# JD1759S-NF-DIS.net
KiCad netlist of a schematic drawn in Altium Designer
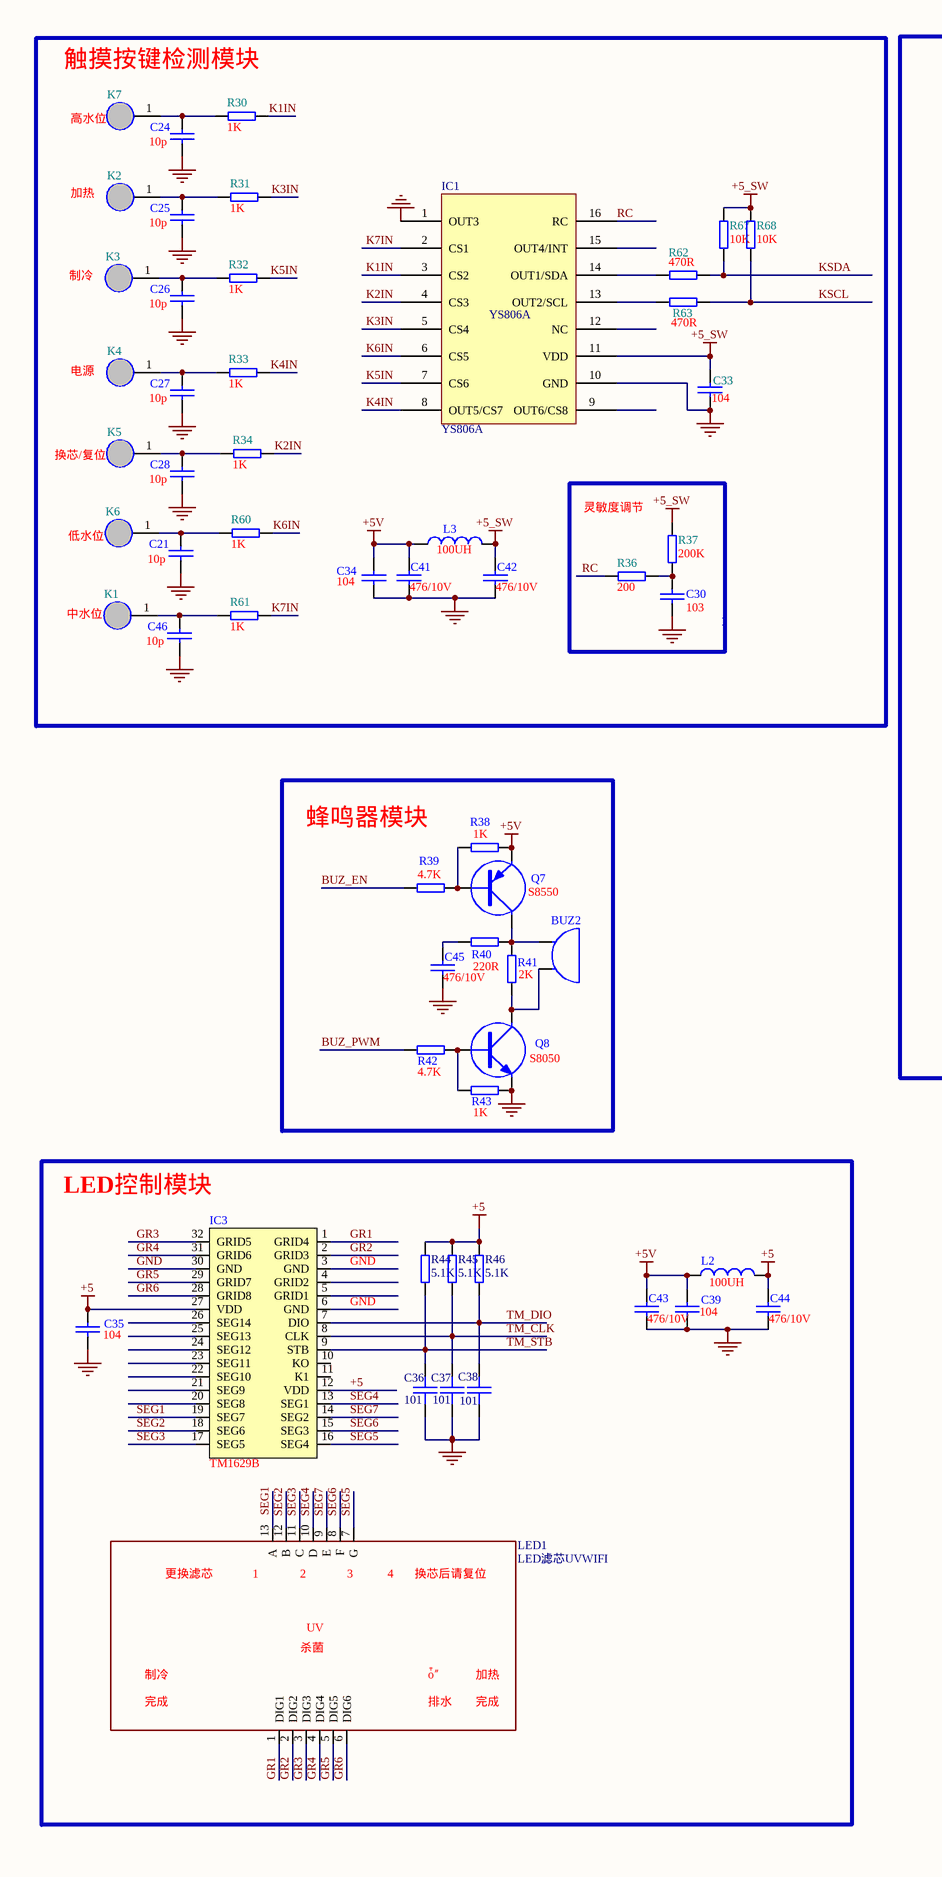
[diagram p0: JD1759S-NF-DIS.SCHDOC, left]
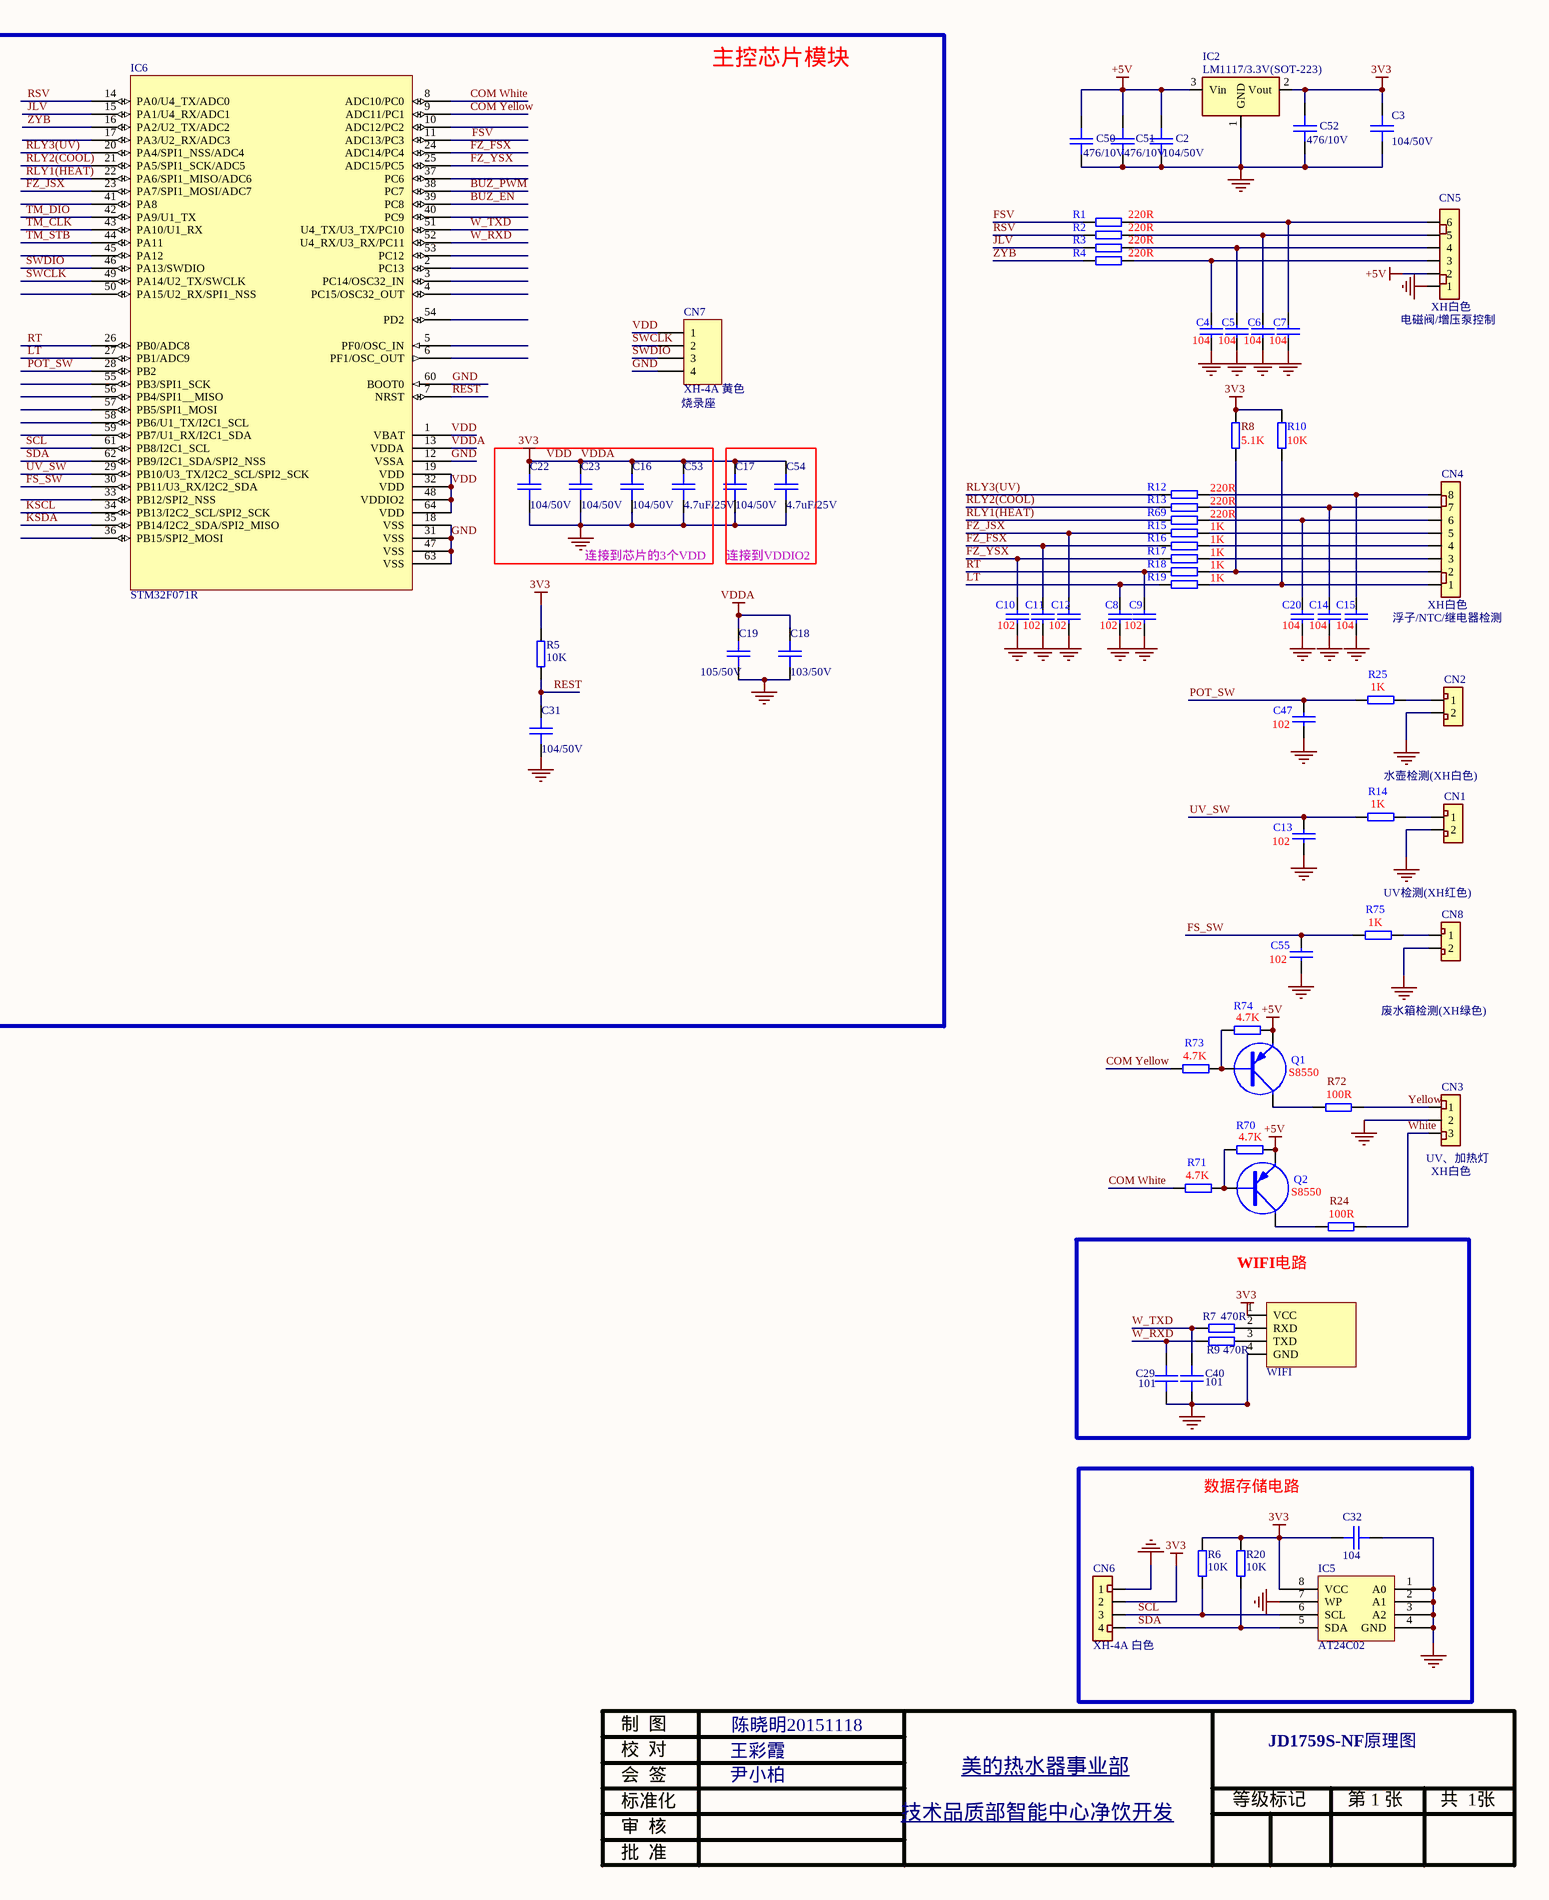
[diagram p1: JD1759S-NF-DIS.SCHDOC, right]

(export (version "E")
  (design (tool "Eeschema 10.0.6"))
  (components
    (comp (ref "BUZ2") (value "~") (footprint "BUZ1") (libsource (lib "*") (part "BUZZER")))
    (comp (ref "C2")
      (value "104/50V")
      (footprint "C0805XG")
      (description "Capacitor")
      (libsource (lib "20131014 MD-SCH") (part "Cap"))
    )
    (comp (ref "C3")
      (value "104/50V")
      (footprint "C0805XG")
      (description "Capacitor (Semiconductor SIM Model)")
      (fields (field (name "PUBLISHER") "*"))
      (libsource (lib "") (part "Cap_1"))
    )
    (comp (ref "C4")
      (value "104")
      (footprint "C0805XG")
      (description "Capacitor")
      (libsource (lib "*") (part "CAP"))
    )
    (comp (ref "C5")
      (value "104")
      (footprint "C0805XG")
      (description "Capacitor")
      (libsource (lib "*") (part "CAP"))
    )
    (comp (ref "C6")
      (value "104")
      (footprint "C0805XG")
      (description "Capacitor")
      (libsource (lib "*") (part "CAP"))
    )
    (comp (ref "C7")
      (value "104")
      (footprint "C0805XG")
      (description "Capacitor")
      (libsource (lib "*") (part "CAP"))
    )
    (comp (ref "C8")
      (value "102")
      (footprint "C0805XG")
      (description "Capacitor")
      (libsource (lib "*") (part "CAP"))
    )
    (comp (ref "C9")
      (value "102")
      (footprint "C0805XG")
      (description "Capacitor")
      (libsource (lib "*") (part "CAP"))
    )
    (comp (ref "C10")
      (value "102")
      (footprint "C0805XG")
      (description "Capacitor")
      (libsource (lib "*") (part "CAP"))
    )
    (comp (ref "C11")
      (value "102")
      (footprint "C0805XG")
      (description "Capacitor")
      (libsource (lib "*") (part "CAP"))
    )
    (comp (ref "C12")
      (value "102")
      (footprint "C0805XG")
      (description "Capacitor")
      (libsource (lib "*") (part "CAP"))
    )
    (comp (ref "C13")
      (value "102")
      (footprint "C0805XG")
      (description "Capacitor")
      (libsource (lib "*") (part "CAP"))
    )
    (comp (ref "C14")
      (value "104")
      (footprint "C0805XG")
      (description "Capacitor")
      (libsource (lib "*") (part "CAP"))
    )
    (comp (ref "C15")
      (value "104")
      (footprint "C0805XG")
      (description "Capacitor")
      (libsource (lib "*") (part "CAP"))
    )
    (comp (ref "C16")
      (value "104/50V")
      (footprint "C0805XG")
      (description "Capacitor")
      (libsource (lib "*") (part "Cap"))
    )
    (comp (ref "C17")
      (value "104/50V")
      (footprint "C0805XG")
      (description "Capacitor")
      (libsource (lib "*") (part "Cap"))
    )
    (comp (ref "C18")
      (value "103/50V")
      (footprint "C0805XG")
      (description "Capacitor")
      (libsource (lib "*") (part "Cap"))
    )
    (comp (ref "C19")
      (value "105/50V")
      (footprint "C0805XG")
      (description "Capacitor")
      (libsource (lib "*") (part "Cap"))
    )
    (comp (ref "C20")
      (value "104")
      (footprint "C0805XG")
      (description "Capacitor")
      (libsource (lib "*") (part "CAP"))
    )
    (comp (ref "C21")
      (value "10p")
      (footprint "C0805XG")
      (description "Capacitor")
      (libsource (lib "*") (part "CAP"))
    )
    (comp (ref "C22")
      (value "104/50V")
      (footprint "C0805XG")
      (description "Capacitor")
      (libsource (lib "*") (part "Cap"))
    )
    (comp (ref "C23")
      (value "104/50V")
      (footprint "C0805XG")
      (description "Capacitor")
      (libsource (lib "*") (part "Cap"))
    )
    (comp (ref "C24")
      (value "10p")
      (footprint "C0805XG")
      (description "Capacitor")
      (libsource (lib "*") (part "CAP"))
    )
    (comp (ref "C25")
      (value "10p")
      (footprint "C0805XG")
      (description "Capacitor")
      (libsource (lib "*") (part "CAP"))
    )
    (comp (ref "C26")
      (value "10p")
      (footprint "C0805XG")
      (description "Capacitor")
      (libsource (lib "*") (part "CAP"))
    )
    (comp (ref "C27")
      (value "10p")
      (footprint "C0805XG")
      (description "Capacitor")
      (libsource (lib "*") (part "CAP"))
    )
    (comp (ref "C28")
      (value "10p")
      (footprint "C0805XG")
      (description "Capacitor")
      (libsource (lib "*") (part "CAP"))
    )
    (comp (ref "C29")
      (value "101")
      (footprint "C0805XG")
      (description "Capacitor")
      (libsource (lib "") (part "Cap_1"))
    )
    (comp (ref "C30") (value "103") (footprint "C0805XG") (libsource (lib "") (part "CAP_3")))
    (comp (ref "C31")
      (value "104/50V")
      (footprint "C0805XG")
      (description "Capacitor")
      (libsource (lib "*") (part "Cap"))
    )
    (comp (ref "C32")
      (value "104")
      (footprint "C0805XG")
      (description "Capacitor")
      (libsource (lib "") (part "Cap_1"))
    )
    (comp (ref "C33") (value "104") (footprint "C0805XG") (libsource (lib "*") (part "C")))
    (comp (ref "C34") (value "104") (footprint "C0805XG") (libsource (lib "") (part "CAP_1")))
    (comp (ref "C35") (value "104") (footprint "C0805XG") (libsource (lib "") (part "CAP_1")))
    (comp (ref "C36")
      (value "101")
      (footprint "C0805XG")
      (description "CAP")
      (libsource (lib "") (part "CAP_2"))
    )
    (comp (ref "C37")
      (value "101")
      (footprint "C0805XG")
      (description "CAP")
      (libsource (lib "") (part "CAP_2"))
    )
    (comp (ref "C38")
      (value "101")
      (footprint "C0805XG")
      (description "CAP")
      (libsource (lib "") (part "CAP_2"))
    )
    (comp (ref "C39") (value "104") (footprint "C0805XG") (libsource (lib "") (part "CAP_1")))
    (comp (ref "C40")
      (value "101")
      (footprint "C0805XG")
      (description "Capacitor")
      (libsource (lib "") (part "Cap_1"))
    )
    (comp (ref "C41") (value "476/10V") (footprint "C1206") (libsource (lib "") (part "CAP_1")))
    (comp (ref "C42") (value "476/10V") (footprint "C1206") (libsource (lib "") (part "CAP_1")))
    (comp (ref "C43") (value "476/10V") (footprint "C1206") (libsource (lib "") (part "CAP_1")))
    (comp (ref "C44") (value "476/10V") (footprint "C1206") (libsource (lib "") (part "CAP_1")))
    (comp (ref "C45") (value "476/10V") (footprint "C1206") (libsource (lib "") (part "CAP_1")))
    (comp (ref "C46")
      (value "10p")
      (footprint "C0805XG")
      (description "Capacitor")
      (libsource (lib "*") (part "CAP"))
    )
    (comp (ref "C47")
      (value "102")
      (footprint "C0805XG")
      (description "Capacitor")
      (libsource (lib "*") (part "CAP"))
    )
    (comp (ref "C50")
      (value "476/10V")
      (footprint "C1206")
      (description "Capacitor")
      (libsource (lib "20131014 MD-SCH") (part "Cap"))
    )
    (comp (ref "C51")
      (value "476/10V")
      (footprint "C1206")
      (description "Capacitor")
      (libsource (lib "20131014 MD-SCH") (part "Cap"))
    )
    (comp (ref "C52")
      (value "476/10V")
      (footprint "C1206")
      (description "Capacitor")
      (libsource (lib "20131014 MD-SCH") (part "Cap"))
    )
    (comp (ref "C53")
      (value "4.7uF/25V")
      (footprint "C0805XG")
      (description "Capacitor")
      (libsource (lib "*") (part "Cap"))
    )
    (comp (ref "C54")
      (value "4.7uF/25V")
      (footprint "C0805XG")
      (description "Capacitor")
      (libsource (lib "*") (part "Cap"))
    )
    (comp (ref "C55")
      (value "102")
      (footprint "C0805XG")
      (description "Capacitor")
      (libsource (lib "*") (part "CAP"))
    )
    (comp (ref "CN1") (value "CN2") (footprint "CN2") (libsource (lib "20131014 MD-SCH") (part "CN2")))
    (comp (ref "CN2") (value "CN2") (footprint "CN2") (libsource (lib "20131014 MD-SCH") (part "CN2")))
    (comp (ref "CN3") (value "CN3") (footprint "CN3") (libsource (lib "20131014 MD-SCH") (part "CN3")))
    (comp (ref "CN4")
      (value "XH白色")
      (footprint "CN8")
      (description "CN8")
      (libsource (lib "20131014 MD-SCH") (part "CN8"))
    )
    (comp (ref "CN5")
      (value "XH白色")
      (footprint "CN6")
      (description "CN6")
      (libsource (lib "20131014 MD-SCH") (part "CN6"))
    )
    (comp (ref "CN6")
      (value "XH-4A 白色")
      (footprint "CN4")
      (description "CN4")
      (libsource (lib "20131014 MD-SCH") (part "CN4"))
    )
    (comp (ref "CN7")
      (value "XH-4A 黄色")
      (footprint "CN4")
      (description "Header, 4-Pin")
      (fields (field (name "PUBLISHER") "Altium Limited"))
      (libsource (lib "*") (part "Header 4"))
    )
    (comp (ref "CN8") (value "CN2") (footprint "CN2") (libsource (lib "20131014 MD-SCH") (part "CN2")))
    (comp (ref "IC1")
      (value "YS806A")
      (footprint "SOP16")
      (libsource (lib "20131014 MD-SCH") (part "YS806A"))
    )
    (comp (ref "IC2")
      (value "LM1117/3.3V(SOT-223)")
      (footprint "SOT-223")
      (libsource (lib "*") (part "SOT-223"))
    )
    (comp (ref "IC3") (value "TM1629B") (footprint "SOP32") (libsource (lib "*") (part "TM1629B")))
    (comp (ref "IC4") (value "WIFI") (footprint "WIFI") (libsource (lib "xxyj_schlib") (part "WIFI")))
    (comp (ref "IC5") (value "AT24C02") (footprint "SOP8") (libsource (lib "*") (part "Component_1")))
    (comp (ref "IC6")
      (value "STM32F071R")
      (footprint "QFP64(0.5MM)")
      (libsource (lib "*") (part "STM32F071R"))
    )
    (comp (ref "K1") (value "中水位") (footprint "KEY-T1 - 12") (libsource (lib "*") (part "1P-TOUCH")))
    (comp (ref "K2") (value "加热") (footprint "KEY-T1 - 12") (libsource (lib "*") (part "1P-TOUCH")))
    (comp (ref "K3") (value "制冷") (footprint "KEY-T1 - 12") (libsource (lib "*") (part "1P-TOUCH")))
    (comp (ref "K4") (value "电源") (footprint "KEY-T1 - 12") (libsource (lib "*") (part "1P-TOUCH")))
    (comp (ref "K5") (value "换芯/复位") (footprint "KEY-T1 - 12") (libsource (lib "*") (part "1P-TOUCH")))
    (comp (ref "K6") (value "低水位") (footprint "KEY-T1 - 12") (libsource (lib "*") (part "1P-TOUCH")))
    (comp (ref "K7") (value "高水位") (footprint "KEY-T1 - 12") (libsource (lib "*") (part "1P-TOUCH")))
    (comp (ref "L2")
      (value "100UH")
      (footprint "L100-5.7")
      (description "LOOP")
      (libsource (lib "*") (part "L-B"))
    )
    (comp (ref "L3")
      (value "100UH")
      (footprint "R1210")
      (description "LOOP")
      (libsource (lib "*") (part "L-B"))
    )
    (comp (ref "LED1")
      (value "LED滤芯UVWIFI")
      (footprint "LED滤芯UVWIFI")
      (description "LED888")
      (libsource (lib "20131014 MD-SCH") (part "LED滤芯UVWIFI"))
    )
    (comp (ref "Q1") (value "S8550") (footprint "SOT23-BCE") (libsource (lib "*") (part "PNP")))
    (comp (ref "Q2") (value "S8550") (footprint "SOT23-BCE") (libsource (lib "*") (part "PNP")))
    (comp (ref "Q7") (value "S8550") (footprint "SOT23-BCE") (libsource (lib "*") (part "PNP")))
    (comp (ref "Q8") (value "S8050") (footprint "SOT23-BCE") (libsource (lib "*") (part "NPN")))
    (comp (ref "R1")
      (value "220R")
      (footprint "R0805XG")
      (description "RES")
      (libsource (lib "*") (part "RES1"))
    )
    (comp (ref "R2")
      (value "220R")
      (footprint "R0805XG")
      (description "RES")
      (libsource (lib "*") (part "RES1"))
    )
    (comp (ref "R3")
      (value "220R")
      (footprint "R0805XG")
      (description "RES")
      (libsource (lib "*") (part "RES1"))
    )
    (comp (ref "R4")
      (value "220R")
      (footprint "R0805XG")
      (description "RES")
      (libsource (lib "*") (part "RES1"))
    )
    (comp (ref "R5")
      (value "10K")
      (footprint "R0805XG")
      (description "RES")
      (libsource (lib "*") (part "RES1"))
    )
    (comp (ref "R6")
      (value "10K")
      (footprint "R0805XG")
      (description "RES")
      (libsource (lib "*") (part "RES1"))
    )
    (comp (ref "R7")
      (value "470R")
      (footprint "R0805XG")
      (description "RES")
      (libsource (lib "*") (part "RES1"))
    )
    (comp (ref "R8")
      (value "5.1K")
      (footprint "R0805XG")
      (description "RES")
      (libsource (lib "*") (part "RES1"))
    )
    (comp (ref "R9")
      (value "470R")
      (footprint "R0805XG")
      (description "RES")
      (libsource (lib "*") (part "RES1"))
    )
    (comp (ref "R10")
      (value "10K")
      (footprint "R0805XG")
      (description "RES")
      (libsource (lib "*") (part "RES1"))
    )
    (comp (ref "R12")
      (value "220R")
      (footprint "R0805XG")
      (description "RES")
      (libsource (lib "*") (part "RES1"))
    )
    (comp (ref "R13")
      (value "220R")
      (footprint "R0805XG")
      (description "RES")
      (libsource (lib "*") (part "RES1"))
    )
    (comp (ref "R14")
      (value "1K")
      (footprint "R0805XG")
      (description "RES")
      (libsource (lib "*") (part "RES1"))
    )
    (comp (ref "R15")
      (value "1K")
      (footprint "R0805XG")
      (description "RES")
      (libsource (lib "*") (part "RES1"))
    )
    (comp (ref "R16")
      (value "1K")
      (footprint "R0805XG")
      (description "RES")
      (libsource (lib "*") (part "RES1"))
    )
    (comp (ref "R17")
      (value "1K")
      (footprint "R0805XG")
      (description "RES")
      (libsource (lib "*") (part "RES1"))
    )
    (comp (ref "R18")
      (value "1K")
      (footprint "R0805XG")
      (description "RES")
      (libsource (lib "*") (part "RES1"))
    )
    (comp (ref "R19")
      (value "1K")
      (footprint "R0805XG")
      (description "RES")
      (libsource (lib "*") (part "RES1"))
    )
    (comp (ref "R20")
      (value "10K")
      (footprint "R0805XG")
      (description "RES")
      (libsource (lib "*") (part "RES1"))
    )
    (comp (ref "R24")
      (value "100R")
      (footprint "R1206")
      (description "RES")
      (libsource (lib "*") (part "RES1"))
    )
    (comp (ref "R25")
      (value "1K")
      (footprint "R0805XG")
      (description "RES")
      (libsource (lib "*") (part "RES1"))
    )
    (comp (ref "R30")
      (value "1K")
      (footprint "R0805XG")
      (description "RES")
      (libsource (lib "*") (part "RES1"))
    )
    (comp (ref "R31")
      (value "1K")
      (footprint "R0805XG")
      (description "RES")
      (libsource (lib "*") (part "RES1"))
    )
    (comp (ref "R32")
      (value "1K")
      (footprint "R0805XG")
      (description "RES")
      (libsource (lib "*") (part "RES1"))
    )
    (comp (ref "R33")
      (value "1K")
      (footprint "R0805XG")
      (description "RES")
      (libsource (lib "*") (part "RES1"))
    )
    (comp (ref "R34")
      (value "1K")
      (footprint "R0805XG")
      (description "RES")
      (libsource (lib "*") (part "RES1"))
    )
    (comp (ref "R36")
      (value "200")
      (footprint "R0805XG")
      (description "RES")
      (libsource (lib "*") (part "RES1"))
    )
    (comp (ref "R37")
      (value "200K")
      (footprint "R0805XG")
      (description "RES")
      (libsource (lib "*") (part "RES1"))
    )
    (comp (ref "R38")
      (value "1K")
      (footprint "R0805XG")
      (description "RES")
      (libsource (lib "*") (part "RES1"))
    )
    (comp (ref "R39")
      (value "4.7K")
      (footprint "R0805XG")
      (description "RES")
      (libsource (lib "*") (part "RES1"))
    )
    (comp (ref "R40")
      (value "220R")
      (footprint "R0805XG")
      (description "RES")
      (libsource (lib "*") (part "RES1"))
    )
    (comp (ref "R41")
      (value "2K")
      (footprint "R0805XG")
      (description "RES")
      (libsource (lib "*") (part "RES1"))
    )
    (comp (ref "R42")
      (value "4.7K")
      (footprint "R0805XG")
      (description "RES")
      (libsource (lib "*") (part "RES1"))
    )
    (comp (ref "R43")
      (value "1K")
      (footprint "R0805XG")
      (description "RES")
      (libsource (lib "*") (part "RES1"))
    )
    (comp (ref "R44")
      (value "5.1K")
      (footprint "R0805XG")
      (description "RES")
      (libsource (lib "*") (part "RES1"))
    )
    (comp (ref "R45")
      (value "5.1K")
      (footprint "R0805XG")
      (description "RES")
      (libsource (lib "*") (part "RES1"))
    )
    (comp (ref "R46")
      (value "5.1K")
      (footprint "R0805XG")
      (description "RES")
      (libsource (lib "*") (part "RES1"))
    )
    (comp (ref "R60")
      (value "1K")
      (footprint "R0805XG")
      (description "RES")
      (libsource (lib "*") (part "RES1"))
    )
    (comp (ref "R61")
      (value "1K")
      (footprint "R0805XG")
      (description "RES")
      (libsource (lib "*") (part "RES1"))
    )
    (comp (ref "R62")
      (value "470R")
      (footprint "R0805XG")
      (description "RES")
      (libsource (lib "*") (part "RES1"))
    )
    (comp (ref "R63")
      (value "470R")
      (footprint "R0805XG")
      (description "RES")
      (libsource (lib "*") (part "RES1"))
    )
    (comp (ref "R67")
      (value "10K")
      (footprint "R0805XG")
      (description "RES")
      (libsource (lib "*") (part "RES1"))
    )
    (comp (ref "R68")
      (value "10K")
      (footprint "R0805XG")
      (description "RES")
      (libsource (lib "*") (part "RES1"))
    )
    (comp (ref "R69")
      (value "220R")
      (footprint "R0805XG")
      (description "RES")
      (libsource (lib "*") (part "RES1"))
    )
    (comp (ref "R70")
      (value "4.7K")
      (footprint "R0805XG")
      (description "RES")
      (libsource (lib "*") (part "RES1"))
    )
    (comp (ref "R71")
      (value "4.7K")
      (footprint "R0805XG")
      (description "RES")
      (libsource (lib "*") (part "RES1"))
    )
    (comp (ref "R72")
      (value "100R")
      (footprint "R1206")
      (description "RES")
      (libsource (lib "*") (part "RES1"))
    )
    (comp (ref "R73")
      (value "4.7K")
      (footprint "R0805XG")
      (description "RES")
      (libsource (lib "*") (part "RES1"))
    )
    (comp (ref "R74")
      (value "4.7K")
      (footprint "R0805XG")
      (description "RES")
      (libsource (lib "*") (part "RES1"))
    )
    (comp (ref "R75")
      (value "1K")
      (footprint "R0805XG")
      (description "RES")
      (libsource (lib "*") (part "RES1"))
    )
  )
  (nets
    (net (code "1") (name "+5") (class "Default")
      (node (ref "C35") (pin "2") (pintype "passive"))
      (node (ref "C44") (pin "2") (pintype "passive"))
      (node (ref "IC3") (pin "12") (pinfunction "VDD_12") (pintype "passive"))
      (node (ref "IC3") (pin "27") (pinfunction "VDD_27") (pintype "passive"))
      (node (ref "L2") (pin "1") (pinfunction "1_1") (pintype "passive"))
      (node (ref "R44") (pin "2") (pinfunction "2_2") (pintype "passive"))
      (node (ref "R45") (pin "2") (pinfunction "2_2") (pintype "passive"))
      (node (ref "R46") (pin "2") (pinfunction "2_2") (pintype "passive"))
    )
    (net (code "2") (name "+5V") (class "Default")
      (node (ref "C2") (pin "2") (pinfunction "2_2") (pintype "passive"))
      (node (ref "C34") (pin "2") (pintype "passive"))
      (node (ref "C39") (pin "2") (pintype "passive"))
      (node (ref "C41") (pin "2") (pintype "passive"))
      (node (ref "C43") (pin "2") (pintype "passive"))
      (node (ref "C50") (pin "2") (pinfunction "2_2") (pintype "passive"))
      (node (ref "C51") (pin "2") (pinfunction "2_2") (pintype "passive"))
      (node (ref "CN5") (pin "2") (pinfunction "2_2") (pintype "passive"))
      (node (ref "IC2") (pin "3") (pinfunction "Vin_3") (pintype "passive"))
      (node (ref "L2") (pin "2") (pinfunction "2_2") (pintype "passive"))
      (node (ref "L3") (pin "2") (pinfunction "2_2") (pintype "passive"))
      (node (ref "Q1") (pin "E") (pintype "passive"))
      (node (ref "Q2") (pin "E") (pintype "passive"))
      (node (ref "Q7") (pin "E") (pintype "passive"))
      (node (ref "R38") (pin "2") (pinfunction "2_2") (pintype "passive"))
      (node (ref "R70") (pin "2") (pinfunction "2_2") (pintype "passive"))
      (node (ref "R74") (pin "2") (pinfunction "2_2") (pintype "passive"))
    )
    (net (code "3") (name "+5_SW") (class "Default")
      (node (ref "C33") (pin "2") (pintype "passive"))
      (node (ref "C42") (pin "2") (pintype "passive"))
      (node (ref "IC1") (pin "11") (pinfunction "VDD_11") (pintype "passive"))
      (node (ref "L3") (pin "1") (pinfunction "1_1") (pintype "passive"))
      (node (ref "R37") (pin "1") (pinfunction "1_1") (pintype "passive"))
      (node (ref "R67") (pin "1") (pinfunction "1_1") (pintype "passive"))
      (node (ref "R68") (pin "1") (pinfunction "1_1") (pintype "passive"))
    )
    (net (code "5") (name "/BUZ_EN") (class "Default")
      (node (ref "IC6") (pin "39") (pinfunction "PC8_39") (pintype "bidirectional"))
      (node (ref "R39") (pin "1") (pinfunction "1_1") (pintype "passive"))
    )
    (net (code "6") (name "/BUZ_PWM") (class "Default")
      (node (ref "IC6") (pin "38") (pinfunction "PC7_38") (pintype "bidirectional"))
      (node (ref "R42") (pin "1") (pinfunction "1_1") (pintype "passive"))
    )
    (net (code "7") (name "/COM White") (class "Default")
      (node (ref "IC6") (pin "8") (pinfunction "ADC10/PC0_8") (pintype "bidirectional"))
      (node (ref "R71") (pin "1") (pinfunction "1_1") (pintype "passive"))
    )
    (net (code "8") (name "/COM Yellow") (class "Default")
      (node (ref "IC6") (pin "9") (pinfunction "ADC11/PC1_9") (pintype "bidirectional"))
      (node (ref "R73") (pin "1") (pinfunction "1_1") (pintype "passive"))
    )
    (net (code "9") (name "/FSV") (class "Default")
      (node (ref "IC6") (pin "11") (pinfunction "ADC13/PC3_11") (pintype "bidirectional"))
      (node (ref "R1") (pin "2") (pinfunction "2_2") (pintype "passive"))
    )
    (net (code "10") (name "/FS_SW") (class "Default")
      (node (ref "C55") (pin "1") (pinfunction "1_1") (pintype "passive"))
      (node (ref "IC6") (pin "30") (pinfunction "PB11/U3_RX/I2C2_SDA_30") (pintype "bidirectional"))
      (node (ref "R75") (pin "2") (pinfunction "2_2") (pintype "passive"))
    )
    (net (code "11") (name "/FZ_FSX") (class "Default")
      (node (ref "C11") (pin "1") (pinfunction "1_1") (pintype "passive"))
      (node (ref "IC6") (pin "24") (pinfunction "ADC14/PC4_24") (pintype "bidirectional"))
      (node (ref "R16") (pin "2") (pinfunction "2_2") (pintype "passive"))
    )
    (net (code "12") (name "/FZ_JSX") (class "Default")
      (node (ref "C12") (pin "1") (pinfunction "1_1") (pintype "passive"))
      (node (ref "IC6") (pin "23") (pinfunction "PA7/SPI1_MOSI/ADC7_23") (pintype "bidirectional"))
      (node (ref "R15") (pin "2") (pinfunction "2_2") (pintype "passive"))
    )
    (net (code "13") (name "/FZ_YSX") (class "Default")
      (node (ref "C10") (pin "1") (pinfunction "1_1") (pintype "passive"))
      (node (ref "IC6") (pin "25") (pinfunction "ADC15/PC5_25") (pintype "bidirectional"))
      (node (ref "R17") (pin "2") (pinfunction "2_2") (pintype "passive"))
    )
    (net (code "14") (name "/GR1") (class "Default")
      (node (ref "IC3") (pin "1") (pinfunction "GRID4_1") (pintype "passive"))
      (node (ref "LED1") (pin "1") (pinfunction "DIG1_1") (pintype "passive"))
    )
    (net (code "15") (name "/GR2") (class "Default")
      (node (ref "IC3") (pin "2") (pinfunction "GRID3_2") (pintype "passive"))
      (node (ref "LED1") (pin "2") (pinfunction "DIG2_2") (pintype "passive"))
    )
    (net (code "16") (name "/GR3") (class "Default")
      (node (ref "IC3") (pin "32") (pinfunction "GRID5_32") (pintype "passive"))
      (node (ref "LED1") (pin "3") (pinfunction "DIG3_3") (pintype "passive"))
    )
    (net (code "17") (name "/GR4") (class "Default")
      (node (ref "IC3") (pin "31") (pinfunction "GRID6_31") (pintype "passive"))
      (node (ref "LED1") (pin "4") (pinfunction "DIG4_4") (pintype "passive"))
    )
    (net (code "18") (name "/GR5") (class "Default")
      (node (ref "IC3") (pin "29") (pinfunction "GRID7_29") (pintype "passive"))
      (node (ref "LED1") (pin "5") (pinfunction "DIG5_5") (pintype "passive"))
    )
    (net (code "19") (name "/GR6") (class "Default")
      (node (ref "IC3") (pin "28") (pinfunction "GRID8_28") (pintype "passive"))
      (node (ref "LED1") (pin "6") (pinfunction "DIG6_6") (pintype "passive"))
    )
    (net (code "20") (name "/JLV") (class "Default")
      (node (ref "IC6") (pin "15") (pinfunction "PA1/U4_RX/ADC1_15") (pintype "bidirectional"))
      (node (ref "R3") (pin "2") (pinfunction "2_2") (pintype "passive"))
    )
    (net (code "21") (name "/K1IN") (class "Default")
      (node (ref "IC1") (pin "3") (pinfunction "CS2_3") (pintype "passive"))
      (node (ref "R30") (pin "2") (pinfunction "2_2") (pintype "passive"))
    )
    (net (code "22") (name "/K2IN") (class "Default")
      (node (ref "IC1") (pin "4") (pinfunction "CS3_4") (pintype "passive"))
      (node (ref "R34") (pin "1") (pinfunction "1_1") (pintype "passive"))
    )
    (net (code "23") (name "/K3IN") (class "Default")
      (node (ref "IC1") (pin "5") (pinfunction "CS4_5") (pintype "passive"))
      (node (ref "R31") (pin "1") (pinfunction "1_1") (pintype "passive"))
    )
    (net (code "24") (name "/K4IN") (class "Default")
      (node (ref "IC1") (pin "8") (pinfunction "OUT5/CS7_8") (pintype "passive"))
      (node (ref "R33") (pin "1") (pinfunction "1_1") (pintype "passive"))
    )
    (net (code "25") (name "/K5IN") (class "Default")
      (node (ref "IC1") (pin "7") (pinfunction "CS6_7") (pintype "passive"))
      (node (ref "R32") (pin "1") (pinfunction "1_1") (pintype "passive"))
    )
    (net (code "26") (name "/K6IN") (class "Default")
      (node (ref "IC1") (pin "6") (pinfunction "CS5_6") (pintype "passive"))
      (node (ref "R60") (pin "1") (pinfunction "1_1") (pintype "passive"))
    )
    (net (code "27") (name "/K7IN") (class "Default")
      (node (ref "IC1") (pin "2") (pinfunction "CS1_2") (pintype "passive"))
      (node (ref "R61") (pin "1") (pinfunction "1_1") (pintype "passive"))
    )
    (net (code "28") (name "/KSCL") (class "Default")
      (node (ref "IC6") (pin "34") (pinfunction "PB13/I2C2_SCL/SPI2_SCK_34") (pintype "bidirectional"))
      (node (ref "R63") (pin "1") (pinfunction "1_1") (pintype "passive"))
      (node (ref "R68") (pin "2") (pinfunction "2_2") (pintype "passive"))
    )
    (net (code "29") (name "/KSDA") (class "Default")
      (node (ref "IC6") (pin "35") (pinfunction "PB14/I2C2_SDA/SPI2_MISO_35") (pintype "bidirectional"))
      (node (ref "R62") (pin "1") (pinfunction "1_1") (pintype "passive"))
      (node (ref "R67") (pin "2") (pinfunction "2_2") (pintype "passive"))
    )
    (net (code "30") (name "/LT") (class "Default")
      (node (ref "C8") (pin "1") (pinfunction "1_1") (pintype "passive"))
      (node (ref "IC6") (pin "27") (pinfunction "PB1/ADC9_27") (pintype "bidirectional"))
      (node (ref "R19") (pin "2") (pinfunction "2_2") (pintype "passive"))
    )
    (net (code "31") (name "/POT_SW") (class "Default")
      (node (ref "C47") (pin "1") (pinfunction "1_1") (pintype "passive"))
      (node (ref "IC6") (pin "28") (pinfunction "PB2_28") (pintype "bidirectional"))
      (node (ref "R25") (pin "2") (pinfunction "2_2") (pintype "passive"))
    )
    (net (code "32") (name "/RC") (class "Default")
      (node (ref "IC1") (pin "16") (pinfunction "RC_16") (pintype "passive"))
      (node (ref "R36") (pin "1") (pinfunction "1_1") (pintype "passive"))
    )
    (net (code "33") (name "/REST") (class "Default")
      (node (ref "C31") (pin "2") (pinfunction "2_2") (pintype "passive"))
      (node (ref "IC6") (pin "7") (pinfunction "NRST_7") (pintype "bidirectional"))
      (node (ref "R5") (pin "2") (pinfunction "2_2") (pintype "passive"))
    )
    (net (code "34") (name "/RLY1(HEAT)") (class "Default")
      (node (ref "IC6") (pin "22") (pinfunction "PA6/SPI1_MISO/ADC6_22") (pintype "bidirectional"))
      (node (ref "R69") (pin "2") (pinfunction "2_2") (pintype "passive"))
    )
    (net (code "35") (name "/RLY2(COOL)") (class "Default")
      (node (ref "IC6") (pin "21") (pinfunction "PA5/SPI1_SCK/ADC5_21") (pintype "bidirectional"))
      (node (ref "R13") (pin "2") (pinfunction "2_2") (pintype "passive"))
    )
    (net (code "36") (name "/RLY3(UV)") (class "Default")
      (node (ref "IC6") (pin "20") (pinfunction "PA4/SPI1_NSS/ADC4_20") (pintype "bidirectional"))
      (node (ref "R12") (pin "2") (pinfunction "2_2") (pintype "passive"))
    )
    (net (code "37") (name "/RSV") (class "Default")
      (node (ref "IC6") (pin "14") (pinfunction "PA0/U4_TX/ADC0_14") (pintype "bidirectional"))
      (node (ref "R2") (pin "2") (pinfunction "2_2") (pintype "passive"))
    )
    (net (code "38") (name "/RT") (class "Default")
      (node (ref "C9") (pin "1") (pinfunction "1_1") (pintype "passive"))
      (node (ref "IC6") (pin "26") (pinfunction "PB0/ADC8_26") (pintype "bidirectional"))
      (node (ref "R18") (pin "2") (pinfunction "2_2") (pintype "passive"))
    )
    (net (code "39") (name "/SCL") (class "Default")
      (node (ref "CN6") (pin "3") (pinfunction "3_3") (pintype "passive"))
      (node (ref "IC5") (pin "6") (pinfunction "SCL_6") (pintype "passive"))
      (node (ref "IC6") (pin "61") (pinfunction "PB8/I2C1_SCL_61") (pintype "bidirectional"))
      (node (ref "R6") (pin "1") (pinfunction "1_1") (pintype "passive"))
    )
    (net (code "40") (name "/SDA") (class "Default")
      (node (ref "CN6") (pin "4") (pinfunction "4_4") (pintype "passive"))
      (node (ref "IC5") (pin "5") (pinfunction "SDA_5") (pintype "passive"))
      (node (ref "IC6") (pin "62") (pinfunction "PB9/I2C1_SDA/SPI2_NSS_62") (pintype "bidirectional"))
      (node (ref "R20") (pin "1") (pinfunction "1_1") (pintype "passive"))
    )
    (net (code "41") (name "/SEG1") (class "Default")
      (node (ref "IC3") (pin "19") (pinfunction "SEG7_19") (pintype "passive"))
      (node (ref "LED1") (pin "13") (pinfunction "A_13") (pintype "passive"))
    )
    (net (code "42") (name "/SEG2") (class "Default")
      (node (ref "IC3") (pin "18") (pinfunction "SEG6_18") (pintype "passive"))
      (node (ref "LED1") (pin "12") (pinfunction "B_12") (pintype "passive"))
    )
    (net (code "43") (name "/SEG3") (class "Default")
      (node (ref "IC3") (pin "17") (pinfunction "SEG5_17") (pintype "passive"))
      (node (ref "LED1") (pin "11") (pinfunction "C_11") (pintype "passive"))
    )
    (net (code "44") (name "/SEG4") (class "Default")
      (node (ref "IC3") (pin "13") (pinfunction "SEG1_13") (pintype "passive"))
      (node (ref "LED1") (pin "10") (pinfunction "D_10") (pintype "passive"))
    )
    (net (code "45") (name "/SEG5") (class "Default")
      (node (ref "IC3") (pin "16") (pinfunction "SEG4_16") (pintype "passive"))
      (node (ref "LED1") (pin "7") (pinfunction "G_7") (pintype "passive"))
    )
    (net (code "46") (name "/SEG6") (class "Default")
      (node (ref "IC3") (pin "15") (pinfunction "SEG3_15") (pintype "passive"))
      (node (ref "LED1") (pin "8") (pinfunction "F_8") (pintype "passive"))
    )
    (net (code "47") (name "/SEG7") (class "Default")
      (node (ref "IC3") (pin "14") (pinfunction "SEG2_14") (pintype "passive"))
      (node (ref "LED1") (pin "9") (pinfunction "E_9") (pintype "passive"))
    )
    (net (code "48") (name "/SWCLK") (class "Default")
      (node (ref "CN7") (pin "2") (pinfunction "2_2") (pintype "passive"))
      (node (ref "IC6") (pin "49") (pinfunction "PA14/U2_TX/SWCLK_49") (pintype "bidirectional"))
    )
    (net (code "49") (name "/SWDIO") (class "Default")
      (node (ref "CN7") (pin "3") (pinfunction "3_3") (pintype "passive"))
      (node (ref "IC6") (pin "46") (pinfunction "PA13/SWDIO_46") (pintype "bidirectional"))
    )
    (net (code "50") (name "/TM_CLK") (class "Default")
      (node (ref "C37") (pin "2") (pinfunction "2_2") (pintype "passive"))
      (node (ref "IC3") (pin "8") (pinfunction "CLK_8") (pintype "passive"))
      (node (ref "IC6") (pin "43") (pinfunction "PA10/U1_RX_43") (pintype "bidirectional"))
      (node (ref "R45") (pin "1") (pinfunction "1_1") (pintype "passive"))
    )
    (net (code "51") (name "/TM_DIO") (class "Default")
      (node (ref "C38") (pin "2") (pinfunction "2_2") (pintype "passive"))
      (node (ref "IC3") (pin "7") (pinfunction "DIO_7") (pintype "passive"))
      (node (ref "IC6") (pin "42") (pinfunction "PA9/U1_TX_42") (pintype "bidirectional"))
      (node (ref "R46") (pin "1") (pinfunction "1_1") (pintype "passive"))
    )
    (net (code "52") (name "/TM_STB") (class "Default")
      (node (ref "C36") (pin "2") (pinfunction "2_2") (pintype "passive"))
      (node (ref "IC3") (pin "9") (pinfunction "STB_9") (pintype "passive"))
      (node (ref "IC6") (pin "44") (pinfunction "PA11_44") (pintype "bidirectional"))
      (node (ref "R44") (pin "1") (pinfunction "1_1") (pintype "passive"))
    )
    (net (code "53") (name "/UV_SW") (class "Default")
      (node (ref "C13") (pin "1") (pinfunction "1_1") (pintype "passive"))
      (node (ref "IC6") (pin "29") (pinfunction "PB10/U3_TX/I2C2_SCL/SPI2_SCK_29") (pintype "bidirectional"))
      (node (ref "R14") (pin "2") (pinfunction "2_2") (pintype "passive"))
    )
    (net (code "54") (name "/W_RXD") (class "Default")
      (node (ref "C29") (pin "2") (pinfunction "2_2") (pintype "passive"))
      (node (ref "IC6") (pin "52") (pinfunction "U4_RX/U3_RX/PC11_52") (pintype "bidirectional"))
      (node (ref "R9") (pin "2") (pinfunction "2_2") (pintype "passive"))
    )
    (net (code "55") (name "/W_TXD") (class "Default")
      (node (ref "C40") (pin "2") (pinfunction "2_2") (pintype "passive"))
      (node (ref "IC6") (pin "51") (pinfunction "U4_TX/U3_TX/PC10_51") (pintype "bidirectional"))
      (node (ref "R7") (pin "2") (pinfunction "2_2") (pintype "passive"))
    )
    (net (code "56") (name "/White") (class "Default")
      (node (ref "CN3") (pin "3") (pinfunction "3_3") (pintype "passive"))
      (node (ref "R24") (pin "2") (pinfunction "2_2") (pintype "passive"))
    )
    (net (code "57") (name "/Yellow") (class "Default")
      (node (ref "CN3") (pin "1") (pinfunction "1_1") (pintype "passive"))
      (node (ref "R72") (pin "2") (pinfunction "2_2") (pintype "passive"))
    )
    (net (code "58") (name "/ZYB") (class "Default")
      (node (ref "IC6") (pin "16") (pinfunction "PA2/U2_TX/ADC2_16") (pintype "bidirectional"))
      (node (ref "R4") (pin "2") (pinfunction "2_2") (pintype "passive"))
    )
    (net (code "59") (name "3V3") (class "Default")
      (node (ref "C16") (pin "2") (pinfunction "2_2") (pintype "passive"))
      (node (ref "C17") (pin "2") (pinfunction "2_2") (pintype "passive"))
      (node (ref "C18") (pin "2") (pinfunction "2_2") (pintype "passive"))
      (node (ref "C19") (pin "2") (pinfunction "2_2") (pintype "passive"))
      (node (ref "C22") (pin "2") (pinfunction "2_2") (pintype "passive"))
      (node (ref "C23") (pin "2") (pinfunction "2_2") (pintype "passive"))
      (node (ref "C3") (pin "1") (pinfunction "1_1") (pintype "passive"))
      (node (ref "C32") (pin "1") (pinfunction "1_1") (pintype "passive"))
      (node (ref "C52") (pin "2") (pinfunction "2_2") (pintype "passive"))
      (node (ref "C53") (pin "2") (pinfunction "2_2") (pintype "passive"))
      (node (ref "C54") (pin "2") (pinfunction "2_2") (pintype "passive"))
      (node (ref "CN6") (pin "2") (pinfunction "2_2") (pintype "passive"))
      (node (ref "CN7") (pin "1") (pinfunction "1_1") (pintype "passive"))
      (node (ref "IC2") (pin "2") (pinfunction "Vout_2") (pintype "passive"))
      (node (ref "IC4") (pin "1") (pinfunction "VCC_1") (pintype "passive"))
      (node (ref "IC5") (pin "8") (pinfunction "VCC_8") (pintype "passive"))
      (node (ref "IC6") (pin "1") (pinfunction "VBAT_1") (pintype "power_in"))
      (node (ref "IC6") (pin "13") (pinfunction "VDDA_13") (pintype "power_in"))
      (node (ref "IC6") (pin "19") (pinfunction "VDD_19") (pintype "power_in"))
      (node (ref "IC6") (pin "32") (pinfunction "VDD_32") (pintype "power_in"))
      (node (ref "IC6") (pin "48") (pinfunction "VDDIO2_48") (pintype "power_in"))
      (node (ref "IC6") (pin "64") (pinfunction "VDD_64") (pintype "power_in"))
      (node (ref "R10") (pin "2") (pinfunction "2_2") (pintype "passive"))
      (node (ref "R20") (pin "2") (pinfunction "2_2") (pintype "passive"))
      (node (ref "R5") (pin "1") (pinfunction "1_1") (pintype "passive"))
      (node (ref "R6") (pin "2") (pinfunction "2_2") (pintype "passive"))
      (node (ref "R8") (pin "2") (pinfunction "2_2") (pintype "passive"))
    )
    (net (code "60") (name "GND") (class "Default")
      (node (ref "C10") (pin "2") (pinfunction "2_2") (pintype "passive"))
      (node (ref "C11") (pin "2") (pinfunction "2_2") (pintype "passive"))
      (node (ref "C12") (pin "2") (pinfunction "2_2") (pintype "passive"))
      (node (ref "C13") (pin "2") (pinfunction "2_2") (pintype "passive"))
      (node (ref "C14") (pin "2") (pinfunction "2_2") (pintype "passive"))
      (node (ref "C15") (pin "2") (pinfunction "2_2") (pintype "passive"))
      (node (ref "C16") (pin "1") (pinfunction "1_1") (pintype "passive"))
      (node (ref "C17") (pin "1") (pinfunction "1_1") (pintype "passive"))
      (node (ref "C18") (pin "1") (pinfunction "1_1") (pintype "passive"))
      (node (ref "C19") (pin "1") (pinfunction "1_1") (pintype "passive"))
      (node (ref "C2") (pin "1") (pinfunction "1_1") (pintype "passive"))
      (node (ref "C20") (pin "2") (pinfunction "2_2") (pintype "passive"))
      (node (ref "C21") (pin "2") (pinfunction "2_2") (pintype "passive"))
      (node (ref "C22") (pin "1") (pinfunction "1_1") (pintype "passive"))
      (node (ref "C23") (pin "1") (pinfunction "1_1") (pintype "passive"))
      (node (ref "C24") (pin "2") (pinfunction "2_2") (pintype "passive"))
      (node (ref "C25") (pin "2") (pinfunction "2_2") (pintype "passive"))
      (node (ref "C26") (pin "2") (pinfunction "2_2") (pintype "passive"))
      (node (ref "C27") (pin "2") (pinfunction "2_2") (pintype "passive"))
      (node (ref "C28") (pin "2") (pinfunction "2_2") (pintype "passive"))
      (node (ref "C29") (pin "1") (pinfunction "1_1") (pintype "passive"))
      (node (ref "C3") (pin "2") (pinfunction "2_2") (pintype "passive"))
      (node (ref "C30") (pin "2") (pintype "passive"))
      (node (ref "C31") (pin "1") (pinfunction "1_1") (pintype "passive"))
      (node (ref "C32") (pin "2") (pinfunction "2_2") (pintype "passive"))
      (node (ref "C33") (pin "1") (pintype "passive"))
      (node (ref "C34") (pin "1") (pintype "passive"))
      (node (ref "C35") (pin "1") (pintype "passive"))
      (node (ref "C36") (pin "1") (pinfunction "1_1") (pintype "passive"))
      (node (ref "C37") (pin "1") (pinfunction "1_1") (pintype "passive"))
      (node (ref "C38") (pin "1") (pinfunction "1_1") (pintype "passive"))
      (node (ref "C39") (pin "1") (pintype "passive"))
      (node (ref "C4") (pin "2") (pinfunction "2_2") (pintype "passive"))
      (node (ref "C40") (pin "1") (pinfunction "1_1") (pintype "passive"))
      (node (ref "C41") (pin "1") (pintype "passive"))
      (node (ref "C42") (pin "1") (pintype "passive"))
      (node (ref "C43") (pin "1") (pintype "passive"))
      (node (ref "C44") (pin "1") (pintype "passive"))
      (node (ref "C45") (pin "1") (pintype "passive"))
      (node (ref "C46") (pin "2") (pinfunction "2_2") (pintype "passive"))
      (node (ref "C47") (pin "2") (pinfunction "2_2") (pintype "passive"))
      (node (ref "C5") (pin "2") (pinfunction "2_2") (pintype "passive"))
      (node (ref "C50") (pin "1") (pinfunction "1_1") (pintype "passive"))
      (node (ref "C51") (pin "1") (pinfunction "1_1") (pintype "passive"))
      (node (ref "C52") (pin "1") (pinfunction "1_1") (pintype "passive"))
      (node (ref "C53") (pin "1") (pinfunction "1_1") (pintype "passive"))
      (node (ref "C54") (pin "1") (pinfunction "1_1") (pintype "passive"))
      (node (ref "C55") (pin "2") (pinfunction "2_2") (pintype "passive"))
      (node (ref "C6") (pin "2") (pinfunction "2_2") (pintype "passive"))
      (node (ref "C7") (pin "2") (pinfunction "2_2") (pintype "passive"))
      (node (ref "C8") (pin "2") (pinfunction "2_2") (pintype "passive"))
      (node (ref "C9") (pin "2") (pinfunction "2_2") (pintype "passive"))
      (node (ref "CN1") (pin "2") (pinfunction "2_2") (pintype "passive"))
      (node (ref "CN2") (pin "2") (pinfunction "2_2") (pintype "passive"))
      (node (ref "CN3") (pin "2") (pinfunction "2_2") (pintype "passive"))
      (node (ref "CN5") (pin "1") (pinfunction "1_1") (pintype "passive"))
      (node (ref "CN6") (pin "1") (pinfunction "1_1") (pintype "passive"))
      (node (ref "CN7") (pin "4") (pinfunction "4_4") (pintype "passive"))
      (node (ref "CN8") (pin "2") (pinfunction "2_2") (pintype "passive"))
      (node (ref "IC1") (pin "1") (pinfunction "OUT3_1") (pintype "passive"))
      (node (ref "IC1") (pin "10") (pinfunction "GND_10") (pintype "passive"))
      (node (ref "IC2") (pin "1") (pinfunction "GND_1") (pintype "passive"))
      (node (ref "IC3") (pin "3") (pinfunction "GND_3") (pintype "passive"))
      (node (ref "IC3") (pin "30") (pinfunction "GND_30") (pintype "passive"))
      (node (ref "IC3") (pin "6") (pinfunction "GND_6") (pintype "passive"))
      (node (ref "IC4") (pin "4") (pinfunction "GND_4") (pintype "passive"))
      (node (ref "IC5") (pin "1") (pinfunction "A0_1") (pintype "passive"))
      (node (ref "IC5") (pin "2") (pinfunction "A1_2") (pintype "passive"))
      (node (ref "IC5") (pin "3") (pinfunction "A2_3") (pintype "passive"))
      (node (ref "IC5") (pin "4") (pinfunction "GND_4") (pintype "passive"))
      (node (ref "IC5") (pin "7") (pinfunction "WP_7") (pintype "passive"))
      (node (ref "IC6") (pin "12") (pinfunction "VSSA_12") (pintype "power_in"))
      (node (ref "IC6") (pin "18") (pinfunction "VSS_18") (pintype "power_in"))
      (node (ref "IC6") (pin "31") (pinfunction "VSS_31") (pintype "power_in"))
      (node (ref "IC6") (pin "47") (pinfunction "VSS_47") (pintype "power_in"))
      (node (ref "IC6") (pin "60") (pinfunction "BOOT0_60") (pintype "input"))
      (node (ref "IC6") (pin "63") (pinfunction "VSS_63") (pintype "power_in"))
      (node (ref "Q8") (pin "E") (pintype "passive"))
      (node (ref "R43") (pin "1") (pinfunction "1_1") (pintype "passive"))
    )
    (net (code "61") (name "Net-(BUZ2-Pad1)") (class "Default")
      (node (ref "BUZ2") (pin "1") (pintype "passive"))
      (node (ref "Q7") (pin "C") (pintype "passive"))
      (node (ref "R40") (pin "1") (pinfunction "1_1") (pintype "passive"))
      (node (ref "R41") (pin "2") (pinfunction "2_2") (pintype "passive"))
    )
    (net (code "62") (name "Net-(BUZ2-Pad2)") (class "Default")
      (node (ref "BUZ2") (pin "2") (pintype "passive"))
      (node (ref "Q8") (pin "C") (pintype "passive"))
      (node (ref "R41") (pin "1") (pinfunction "1_1") (pintype "passive"))
    )
    (net (code "63") (name "Net-(C4-Pad1)") (class "Default")
      (node (ref "C4") (pin "1") (pinfunction "1_1") (pintype "passive"))
      (node (ref "CN5") (pin "3") (pinfunction "3_3") (pintype "passive"))
      (node (ref "R4") (pin "1") (pinfunction "1_1") (pintype "passive"))
    )
    (net (code "64") (name "Net-(C5-Pad1)") (class "Default")
      (node (ref "C5") (pin "1") (pinfunction "1_1") (pintype "passive"))
      (node (ref "CN5") (pin "4") (pinfunction "4_4") (pintype "passive"))
      (node (ref "R3") (pin "1") (pinfunction "1_1") (pintype "passive"))
    )
    (net (code "65") (name "Net-(C6-Pad1)") (class "Default")
      (node (ref "C6") (pin "1") (pinfunction "1_1") (pintype "passive"))
      (node (ref "CN5") (pin "5") (pinfunction "5_5") (pintype "passive"))
      (node (ref "R2") (pin "1") (pinfunction "1_1") (pintype "passive"))
    )
    (net (code "66") (name "Net-(C7-Pad1)") (class "Default")
      (node (ref "C7") (pin "1") (pinfunction "1_1") (pintype "passive"))
      (node (ref "CN5") (pin "6") (pinfunction "6_6") (pintype "passive"))
      (node (ref "R1") (pin "1") (pinfunction "1_1") (pintype "passive"))
    )
    (net (code "67") (name "Net-(C14-Pad1)") (class "Default")
      (node (ref "C14") (pin "1") (pinfunction "1_1") (pintype "passive"))
      (node (ref "CN4") (pin "7") (pinfunction "7_7") (pintype "passive"))
      (node (ref "R13") (pin "1") (pinfunction "1_1") (pintype "passive"))
    )
    (net (code "68") (name "Net-(C15-Pad1)") (class "Default")
      (node (ref "C15") (pin "1") (pinfunction "1_1") (pintype "passive"))
      (node (ref "CN4") (pin "8") (pinfunction "8_8") (pintype "passive"))
      (node (ref "R12") (pin "1") (pinfunction "1_1") (pintype "passive"))
    )
    (net (code "69") (name "Net-(C20-Pad1)") (class "Default")
      (node (ref "C20") (pin "1") (pinfunction "1_1") (pintype "passive"))
      (node (ref "CN4") (pin "6") (pinfunction "6_6") (pintype "passive"))
      (node (ref "R69") (pin "1") (pinfunction "1_1") (pintype "passive"))
    )
    (net (code "70") (name "Net-(C30-Pad1)") (class "Default")
      (node (ref "C30") (pin "1") (pintype "passive"))
      (node (ref "R36") (pin "2") (pinfunction "2_2") (pintype "passive"))
      (node (ref "R37") (pin "2") (pinfunction "2_2") (pintype "passive"))
    )
    (net (code "71") (name "Net-(C45-Pad2)") (class "Default")
      (node (ref "C45") (pin "2") (pintype "passive"))
      (node (ref "R40") (pin "2") (pinfunction "2_2") (pintype "passive"))
    )
    (net (code "72") (name "Net-(CN1-Pad1)") (class "Default")
      (node (ref "CN1") (pin "1") (pinfunction "1_1") (pintype "passive"))
      (node (ref "R14") (pin "1") (pinfunction "1_1") (pintype "passive"))
    )
    (net (code "73") (name "Net-(CN2-Pad1)") (class "Default")
      (node (ref "CN2") (pin "1") (pinfunction "1_1") (pintype "passive"))
      (node (ref "R25") (pin "1") (pinfunction "1_1") (pintype "passive"))
    )
    (net (code "74") (name "Net-(CN4-Pad1)") (class "Default")
      (node (ref "CN4") (pin "1") (pinfunction "1_1") (pintype "passive"))
      (node (ref "R10") (pin "1") (pinfunction "1_1") (pintype "passive"))
      (node (ref "R19") (pin "1") (pinfunction "1_1") (pintype "passive"))
    )
    (net (code "75") (name "Net-(CN4-Pad2)") (class "Default")
      (node (ref "CN4") (pin "2") (pinfunction "2_2") (pintype "passive"))
      (node (ref "R18") (pin "1") (pinfunction "1_1") (pintype "passive"))
      (node (ref "R8") (pin "1") (pinfunction "1_1") (pintype "passive"))
    )
    (net (code "76") (name "Net-(CN4-Pad3)") (class "Default")
      (node (ref "CN4") (pin "3") (pinfunction "3_3") (pintype "passive"))
      (node (ref "R17") (pin "1") (pinfunction "1_1") (pintype "passive"))
    )
    (net (code "77") (name "Net-(CN4-Pad4)") (class "Default")
      (node (ref "CN4") (pin "4") (pinfunction "4_4") (pintype "passive"))
      (node (ref "R16") (pin "1") (pinfunction "1_1") (pintype "passive"))
    )
    (net (code "78") (name "Net-(CN4-Pad5)") (class "Default")
      (node (ref "CN4") (pin "5") (pinfunction "5_5") (pintype "passive"))
      (node (ref "R15") (pin "1") (pinfunction "1_1") (pintype "passive"))
    )
    (net (code "79") (name "Net-(CN8-Pad1)") (class "Default")
      (node (ref "CN8") (pin "1") (pinfunction "1_1") (pintype "passive"))
      (node (ref "R75") (pin "1") (pinfunction "1_1") (pintype "passive"))
    )
    (net (code "80") (name "Net-(IC1-OUT1{slash}SDA)") (class "Default")
      (node (ref "IC1") (pin "14") (pinfunction "OUT1/SDA_14") (pintype "passive"))
      (node (ref "R62") (pin "2") (pinfunction "2_2") (pintype "passive"))
    )
    (net (code "81") (name "Net-(IC1-OUT2{slash}SCL)") (class "Default")
      (node (ref "IC1") (pin "13") (pinfunction "OUT2/SCL_13") (pintype "passive"))
      (node (ref "R63") (pin "2") (pinfunction "2_2") (pintype "passive"))
    )
    (net (code "82") (name "Net-(IC4-RXD)") (class "Default")
      (node (ref "IC4") (pin "2") (pinfunction "RXD_2") (pintype "passive"))
      (node (ref "R7") (pin "1") (pinfunction "1_1") (pintype "passive"))
    )
    (net (code "83") (name "Net-(IC4-TXD)") (class "Default")
      (node (ref "IC4") (pin "3") (pinfunction "TXD_3") (pintype "passive"))
      (node (ref "R9") (pin "1") (pinfunction "1_1") (pintype "passive"))
    )
    (net (code "84") (name "Net-(K1-TOUCH_KEY)") (class "Default")
      (node (ref "C46") (pin "1") (pinfunction "1_1") (pintype "passive"))
      (node (ref "K1") (pin "1") (pinfunction "TOUCH_KEY_1") (pintype "passive"))
      (node (ref "R61") (pin "2") (pinfunction "2_2") (pintype "passive"))
    )
    (net (code "85") (name "Net-(K2-TOUCH_KEY)") (class "Default")
      (node (ref "C25") (pin "1") (pinfunction "1_1") (pintype "passive"))
      (node (ref "K2") (pin "1") (pinfunction "TOUCH_KEY_1") (pintype "passive"))
      (node (ref "R31") (pin "2") (pinfunction "2_2") (pintype "passive"))
    )
    (net (code "86") (name "Net-(K3-TOUCH_KEY)") (class "Default")
      (node (ref "C26") (pin "1") (pinfunction "1_1") (pintype "passive"))
      (node (ref "K3") (pin "1") (pinfunction "TOUCH_KEY_1") (pintype "passive"))
      (node (ref "R32") (pin "2") (pinfunction "2_2") (pintype "passive"))
    )
    (net (code "87") (name "Net-(K4-TOUCH_KEY)") (class "Default")
      (node (ref "C27") (pin "1") (pinfunction "1_1") (pintype "passive"))
      (node (ref "K4") (pin "1") (pinfunction "TOUCH_KEY_1") (pintype "passive"))
      (node (ref "R33") (pin "2") (pinfunction "2_2") (pintype "passive"))
    )
    (net (code "88") (name "Net-(K5-TOUCH_KEY)") (class "Default")
      (node (ref "C28") (pin "1") (pinfunction "1_1") (pintype "passive"))
      (node (ref "K5") (pin "1") (pinfunction "TOUCH_KEY_1") (pintype "passive"))
      (node (ref "R34") (pin "2") (pinfunction "2_2") (pintype "passive"))
    )
    (net (code "89") (name "Net-(K6-TOUCH_KEY)") (class "Default")
      (node (ref "C21") (pin "1") (pinfunction "1_1") (pintype "passive"))
      (node (ref "K6") (pin "1") (pinfunction "TOUCH_KEY_1") (pintype "passive"))
      (node (ref "R60") (pin "2") (pinfunction "2_2") (pintype "passive"))
    )
    (net (code "90") (name "Net-(K7-TOUCH_KEY)") (class "Default")
      (node (ref "C24") (pin "1") (pinfunction "1_1") (pintype "passive"))
      (node (ref "K7") (pin "1") (pinfunction "TOUCH_KEY_1") (pintype "passive"))
      (node (ref "R30") (pin "1") (pinfunction "1_1") (pintype "passive"))
    )
    (net (code "91") (name "Net-(Q1-PadB)") (class "Default")
      (node (ref "Q1") (pin "B") (pintype "passive"))
      (node (ref "R73") (pin "2") (pinfunction "2_2") (pintype "passive"))
      (node (ref "R74") (pin "1") (pinfunction "1_1") (pintype "passive"))
    )
    (net (code "92") (name "Net-(Q1-PadC)") (class "Default")
      (node (ref "Q1") (pin "C") (pintype "passive"))
      (node (ref "R72") (pin "1") (pinfunction "1_1") (pintype "passive"))
    )
    (net (code "93") (name "Net-(Q2-PadB)") (class "Default")
      (node (ref "Q2") (pin "B") (pintype "passive"))
      (node (ref "R70") (pin "1") (pinfunction "1_1") (pintype "passive"))
      (node (ref "R71") (pin "2") (pinfunction "2_2") (pintype "passive"))
    )
    (net (code "94") (name "Net-(Q2-PadC)") (class "Default")
      (node (ref "Q2") (pin "C") (pintype "passive"))
      (node (ref "R24") (pin "1") (pinfunction "1_1") (pintype "passive"))
    )
    (net (code "95") (name "Net-(Q7-PadB)") (class "Default")
      (node (ref "Q7") (pin "B") (pintype "passive"))
      (node (ref "R38") (pin "1") (pinfunction "1_1") (pintype "passive"))
      (node (ref "R39") (pin "2") (pinfunction "2_2") (pintype "passive"))
    )
    (net (code "96") (name "Net-(Q8-PadB)") (class "Default")
      (node (ref "Q8") (pin "B") (pintype "passive"))
      (node (ref "R42") (pin "2") (pinfunction "2_2") (pintype "passive"))
      (node (ref "R43") (pin "2") (pinfunction "2_2") (pintype "passive"))
    )
    (net (code "97") (name "unconnected-(IC1-NC-Pad12)") (class "Default")
      (node (ref "IC1") (pin "12") (pinfunction "NC_12") (pintype "passive"))
    )
    (net (code "98") (name "unconnected-(IC1-OUT4{slash}INT-Pad15)") (class "Default")
      (node (ref "IC1") (pin "15") (pinfunction "OUT4/INT_15") (pintype "passive"))
    )
    (net (code "99") (name "unconnected-(IC1-OUT6{slash}CS8-Pad9)") (class "Default")
      (node (ref "IC1") (pin "9") (pinfunction "OUT6/CS8_9") (pintype "passive"))
    )
    (net (code "100") (name "unconnected-(IC3-GRID1-Pad5)") (class "Default")
      (node (ref "IC3") (pin "5") (pinfunction "GRID1_5") (pintype "passive"))
    )
    (net (code "101") (name "unconnected-(IC3-GRID2-Pad4)") (class "Default")
      (node (ref "IC3") (pin "4") (pinfunction "GRID2_4") (pintype "passive"))
    )
    (net (code "102") (name "unconnected-(IC3-K1-Pad11)") (class "Default")
      (node (ref "IC3") (pin "11") (pinfunction "K1_11") (pintype "passive"))
    )
    (net (code "103") (name "unconnected-(IC3-KO-Pad10)") (class "Default")
      (node (ref "IC3") (pin "10") (pinfunction "KO_10") (pintype "passive"))
    )
    (net (code "104") (name "unconnected-(IC3-SEG8-Pad20)") (class "Default")
      (node (ref "IC3") (pin "20") (pinfunction "SEG8_20") (pintype "passive"))
    )
    (net (code "105") (name "unconnected-(IC3-SEG9-Pad21)") (class "Default")
      (node (ref "IC3") (pin "21") (pinfunction "SEG9_21") (pintype "passive"))
    )
    (net (code "106") (name "unconnected-(IC3-SEG10-Pad22)") (class "Default")
      (node (ref "IC3") (pin "22") (pinfunction "SEG10_22") (pintype "passive"))
    )
    (net (code "107") (name "unconnected-(IC3-SEG11-Pad23)") (class "Default")
      (node (ref "IC3") (pin "23") (pinfunction "SEG11_23") (pintype "passive"))
    )
    (net (code "108") (name "unconnected-(IC3-SEG12-Pad24)") (class "Default")
      (node (ref "IC3") (pin "24") (pinfunction "SEG12_24") (pintype "passive"))
    )
    (net (code "109") (name "unconnected-(IC3-SEG13-Pad25)") (class "Default")
      (node (ref "IC3") (pin "25") (pinfunction "SEG13_25") (pintype "passive"))
    )
    (net (code "110") (name "unconnected-(IC3-SEG14-Pad26)") (class "Default")
      (node (ref "IC3") (pin "26") (pinfunction "SEG14_26") (pintype "passive"))
    )
    (net (code "111") (name "unconnected-(IC6-ADC12{slash}PC2-Pad10)") (class "Default")
      (node (ref "IC6") (pin "10") (pinfunction "ADC12/PC2_10") (pintype "bidirectional"))
    )
    (net (code "112") (name "unconnected-(IC6-PA3{slash}U2_RX{slash}ADC3-Pad17)") (class "Default")
      (node (ref "IC6") (pin "17") (pinfunction "PA3/U2_RX/ADC3_17") (pintype "bidirectional"))
    )
    (net (code "113") (name "unconnected-(IC6-PA8-Pad41)") (class "Default")
      (node (ref "IC6") (pin "41") (pinfunction "PA8_41") (pintype "bidirectional"))
    )
    (net (code "114") (name "unconnected-(IC6-PA12-Pad45)") (class "Default")
      (node (ref "IC6") (pin "45") (pinfunction "PA12_45") (pintype "bidirectional"))
    )
    (net (code "115") (name "unconnected-(IC6-PA15{slash}U2_RX{slash}SPI1_NSS-Pad50)") (class "Default")
      (node (ref "IC6") (pin "50") (pinfunction "PA15/U2_RX/SPI1_NSS_50") (pintype "bidirectional"))
    )
    (net (code "116") (name "unconnected-(IC6-PB3{slash}SPI1_SCK-Pad55)") (class "Default")
      (node (ref "IC6") (pin "55") (pinfunction "PB3/SPI1_SCK_55") (pintype "bidirectional"))
    )
    (net (code "117") (name "unconnected-(IC6-PB4{slash}SPI1__MISO-Pad56)") (class "Default")
      (node (ref "IC6") (pin "56") (pinfunction "PB4/SPI1__MISO_56") (pintype "bidirectional"))
    )
    (net (code "118") (name "unconnected-(IC6-PB5{slash}SPI1_MOSI-Pad57)") (class "Default")
      (node (ref "IC6") (pin "57") (pinfunction "PB5/SPI1_MOSI_57") (pintype "bidirectional"))
    )
    (net (code "119") (name "unconnected-(IC6-PB6{slash}U1_TX{slash}I2C1_SCL-Pad58)") (class "Default")
      (node (ref "IC6") (pin "58") (pinfunction "PB6/U1_TX/I2C1_SCL_58") (pintype "bidirectional"))
    )
    (net (code "120") (name "unconnected-(IC6-PB7{slash}U1_RX{slash}I2C1_SDA-Pad59)") (class "Default")
      (node (ref "IC6") (pin "59") (pinfunction "PB7/U1_RX/I2C1_SDA_59") (pintype "bidirectional"))
    )
    (net (code "121") (name "unconnected-(IC6-PB12{slash}SPI2_NSS-Pad33)") (class "Default")
      (node (ref "IC6") (pin "33") (pinfunction "PB12/SPI2_NSS_33") (pintype "bidirectional"))
    )
    (net (code "122") (name "unconnected-(IC6-PB15{slash}SPI2_MOSI-Pad36)") (class "Default")
      (node (ref "IC6") (pin "36") (pinfunction "PB15/SPI2_MOSI_36") (pintype "bidirectional"))
    )
    (net (code "123") (name "unconnected-(IC6-PC6-Pad37)") (class "Default")
      (node (ref "IC6") (pin "37") (pinfunction "PC6_37") (pintype "bidirectional"))
    )
    (net (code "124") (name "unconnected-(IC6-PC9-Pad40)") (class "Default")
      (node (ref "IC6") (pin "40") (pinfunction "PC9_40") (pintype "bidirectional"))
    )
    (net (code "125") (name "unconnected-(IC6-PC12-Pad53)") (class "Default")
      (node (ref "IC6") (pin "53") (pinfunction "PC12_53") (pintype "bidirectional"))
    )
    (net (code "126") (name "unconnected-(IC6-PC13-Pad2)") (class "Default")
      (node (ref "IC6") (pin "2") (pinfunction "PC13_2") (pintype "bidirectional"))
    )
    (net (code "127") (name "unconnected-(IC6-PC14{slash}OSC32_IN-Pad3)") (class "Default")
      (node (ref "IC6") (pin "3") (pinfunction "PC14/OSC32_IN_3") (pintype "bidirectional"))
    )
    (net (code "128") (name "unconnected-(IC6-PC15{slash}OSC32_OUT-Pad4)") (class "Default")
      (node (ref "IC6") (pin "4") (pinfunction "PC15/OSC32_OUT_4") (pintype "bidirectional"))
    )
    (net (code "129") (name "unconnected-(IC6-PD2-Pad54)") (class "Default")
      (node (ref "IC6") (pin "54") (pinfunction "PD2_54") (pintype "bidirectional"))
    )
    (net (code "130") (name "unconnected-(IC6-PF0{slash}OSC_IN-Pad5)") (class "Default")
      (node (ref "IC6") (pin "5") (pinfunction "PF0/OSC_IN_5") (pintype "input"))
    )
    (net (code "131") (name "unconnected-(IC6-PF1{slash}OSC_OUT-Pad6)") (class "Default")
      (node (ref "IC6") (pin "6") (pinfunction "PF1/OSC_OUT_6") (pintype "output"))
    )
  )
)
